# NEW_MD_-.net
KiCad netlist of a schematic drawn in EAGLE
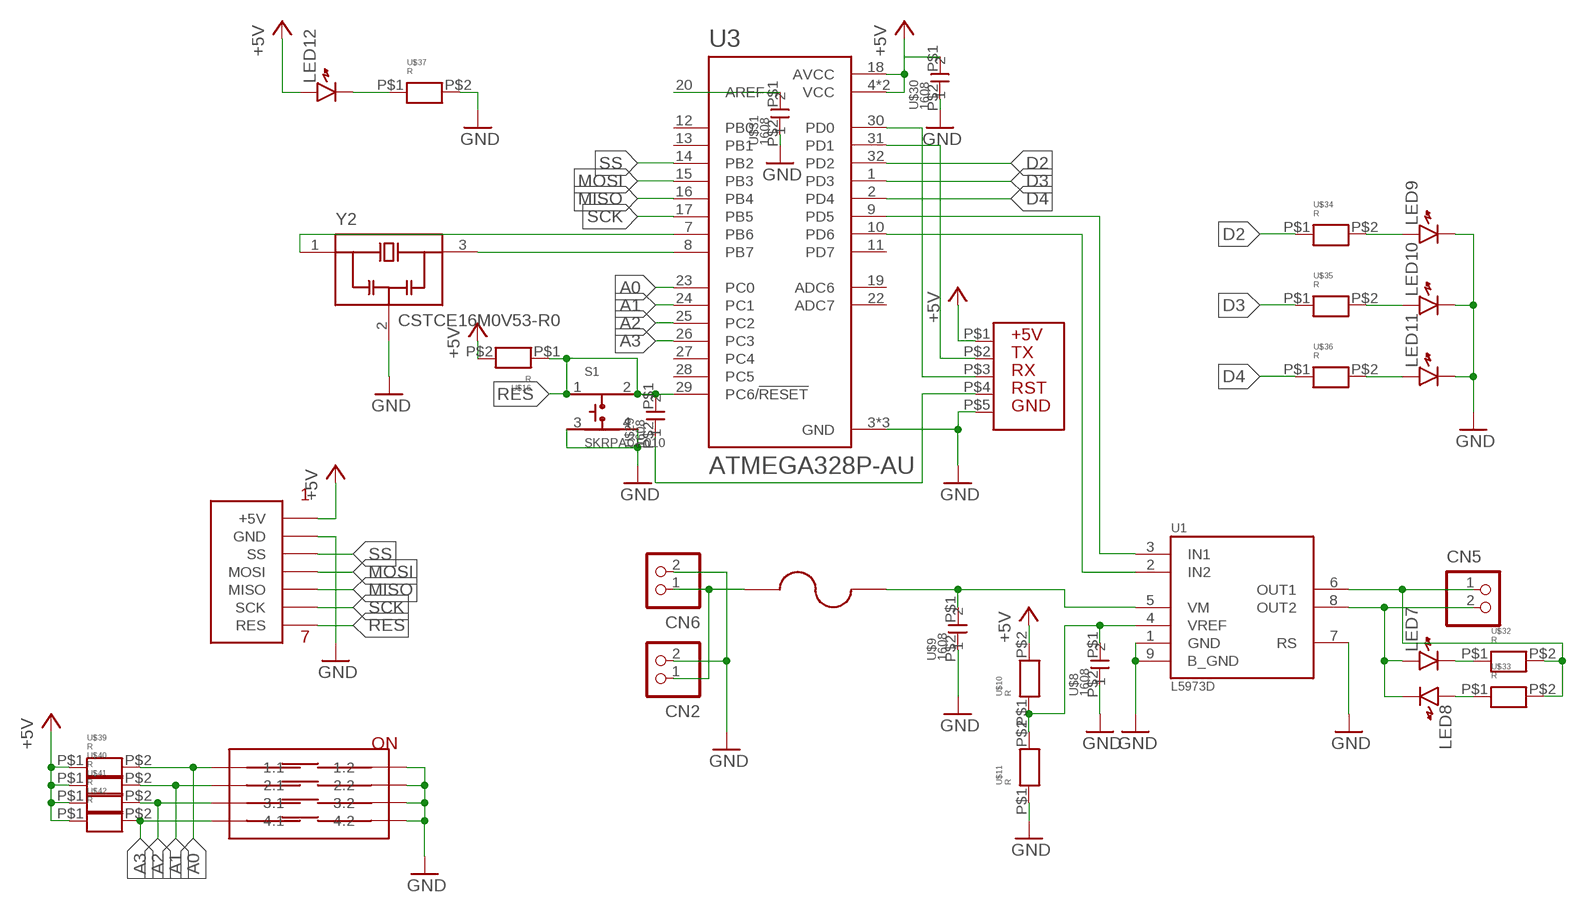
[diagram p0: schematic, sheet 1]

(export (version "E")
  (design (tool "Eeschema 10.0.6"))
  (components
    (comp (ref "CN2")
      (value "B2B-XH-A")
      (footprint "eagle-import:B2B-XH-A")
      (libsource (lib "eagle-import") (part "B2B-XH-A"))
    )
    (comp (ref "CN5")
      (value "S2B-XH-A")
      (footprint "eagle-import:S2B-XH-A")
      (libsource (lib "eagle-import") (part "S2B-XH-A"))
    )
    (comp (ref "CN6")
      (value "B2B-XH-A")
      (footprint "eagle-import:B2B-XH-A")
      (libsource (lib "eagle-import") (part "B2B-XH-A"))
    )
    (comp (ref "LED7")
      (value "LED1608")
      (footprint "eagle-import:LED1608")
      (libsource (lib "eagle-import") (part "LED1608"))
    )
    (comp (ref "LED8")
      (value "LED1608")
      (footprint "eagle-import:LED1608")
      (libsource (lib "eagle-import") (part "LED1608"))
    )
    (comp (ref "LED9")
      (value "LED1608")
      (footprint "eagle-import:LED1608")
      (libsource (lib "eagle-import") (part "LED1608"))
    )
    (comp (ref "LED10")
      (value "LED1608")
      (footprint "eagle-import:LED1608")
      (libsource (lib "eagle-import") (part "LED1608"))
    )
    (comp (ref "LED11")
      (value "LED1608")
      (footprint "eagle-import:LED1608")
      (libsource (lib "eagle-import") (part "LED1608"))
    )
    (comp (ref "LED12")
      (value "LED1608")
      (footprint "eagle-import:LED1608")
      (libsource (lib "eagle-import") (part "LED1608"))
    )
    (comp (ref "S1")
      (value "SKRPACE010")
      (footprint "eagle-import:SW_SKRPACE010")
      (fields (field (name "MF") "ALPS"))
      (libsource (lib "eagle-import") (part "SKRPACE010"))
    )
    (comp (ref "U$1")
      (value "FUSE3.7A")
      (footprint "eagle-import:FUSE3.7A")
      (libsource (lib "eagle-import") (part "FUSE3.7A"))
    )
    (comp (ref "U$8")
      (value "1608")
      (footprint "eagle-import:CON")
      (libsource (lib "eagle-import") (part "1608"))
    )
    (comp (ref "U$9")
      (value "1608")
      (footprint "eagle-import:CON")
      (libsource (lib "eagle-import") (part "1608"))
    )
    (comp (ref "U$10")
      (value "R")
      (footprint "eagle-import:1608")
      (libsource (lib "eagle-import") (part "R"))
    )
    (comp (ref "U$11")
      (value "R")
      (footprint "eagle-import:1608")
      (libsource (lib "eagle-import") (part "R"))
    )
    (comp (ref "U$16")
      (value "R")
      (footprint "eagle-import:1608")
      (libsource (lib "eagle-import") (part "R"))
    )
    (comp (ref "U$29")
      (value "1608")
      (footprint "eagle-import:CON")
      (libsource (lib "eagle-import") (part "1608"))
    )
    (comp (ref "U$30")
      (value "1608")
      (footprint "eagle-import:CON")
      (libsource (lib "eagle-import") (part "1608"))
    )
    (comp (ref "U$31")
      (value "1608")
      (footprint "eagle-import:CON")
      (libsource (lib "eagle-import") (part "1608"))
    )
    (comp (ref "U$32")
      (value "R")
      (footprint "eagle-import:1608")
      (libsource (lib "eagle-import") (part "R"))
    )
    (comp (ref "U$33")
      (value "R")
      (footprint "eagle-import:1608")
      (libsource (lib "eagle-import") (part "R"))
    )
    (comp (ref "U$34")
      (value "R")
      (footprint "eagle-import:1608")
      (libsource (lib "eagle-import") (part "R"))
    )
    (comp (ref "U$35")
      (value "R")
      (footprint "eagle-import:1608")
      (libsource (lib "eagle-import") (part "R"))
    )
    (comp (ref "U$36")
      (value "R")
      (footprint "eagle-import:1608")
      (libsource (lib "eagle-import") (part "R"))
    )
    (comp (ref "U$37")
      (value "R")
      (footprint "eagle-import:1608")
      (libsource (lib "eagle-import") (part "R"))
    )
    (comp (ref "U$38")
      (value "4P")
      (footprint "eagle-import:4P")
      (libsource (lib "eagle-import") (part "4P"))
    )
    (comp (ref "U$39")
      (value "R")
      (footprint "eagle-import:1608")
      (libsource (lib "eagle-import") (part "R"))
    )
    (comp (ref "U$40")
      (value "R")
      (footprint "eagle-import:1608")
      (libsource (lib "eagle-import") (part "R"))
    )
    (comp (ref "U$41")
      (value "R")
      (footprint "eagle-import:1608")
      (libsource (lib "eagle-import") (part "R"))
    )
    (comp (ref "U$42")
      (value "R")
      (footprint "eagle-import:1608")
      (libsource (lib "eagle-import") (part "R"))
    )
    (comp (ref "U$43")
      (value "SPI")
      (footprint "eagle-import:SPI")
      (libsource (lib "eagle-import") (part "SPI"))
    )
    (comp (ref "U$44")
      (value "SI")
      (footprint "eagle-import:SI")
      (libsource (lib "eagle-import") (part "SI"))
    )
    (comp (ref "U1")
      (value "L5973D")
      (footprint "eagle-import:SOIC127P600X170-9N")
      (fields (field (name "MF") "STMicroelectronics"))
      (libsource (lib "eagle-import") (part "L5973D"))
    )
    (comp (ref "U3")
      (value "ATMEGA328P-AU")
      (footprint "eagle-import:QFP80P900X900X120-32N")
      (fields (field (name "MF") "Microchip Technology"))
      (libsource (lib "eagle-import") (part "ATMEGA328P-AU"))
    )
    (comp (ref "Y2")
      (value "CSTCE16M0V53-R0")
      (footprint "eagle-import:OSC_CSTCE16M0V53-R0")
      (fields (field (name "MANUFACTURER") "Murata"))
      (libsource (lib "eagle-import") (part "CSTCE16M0V53-R0"))
    )
  )
  (nets
    (net (code "1") (name "+5V") (class "Default")
      (node (ref "LED12") (pin "A") (pinfunction "A_A") (pintype "passive"))
      (node (ref "U$10") (pin "P$2") (pinfunction "P$2_P$2") (pintype "bidirectional"))
      (node (ref "U$16") (pin "P$2") (pinfunction "P$2_P$2") (pintype "bidirectional"))
      (node (ref "U$30") (pin "P$1") (pinfunction "1_P$1") (pintype "bidirectional"))
      (node (ref "U$39") (pin "P$1") (pinfunction "P$1_P$1") (pintype "bidirectional"))
      (node (ref "U$40") (pin "P$1") (pinfunction "P$1_P$1") (pintype "bidirectional"))
      (node (ref "U$41") (pin "P$1") (pinfunction "P$1_P$1") (pintype "bidirectional"))
      (node (ref "U$42") (pin "P$1") (pinfunction "P$1_P$1") (pintype "bidirectional"))
      (node (ref "U$43") (pin "P$1") (pinfunction "+5V_P$1") (pintype "bidirectional"))
      (node (ref "U$44") (pin "P$1") (pinfunction "P$1_P$1") (pintype "bidirectional"))
      (node (ref "U3") (pin "18") (pinfunction "AVCC_18") (pintype "power_in"))
      (node (ref "U3") (pin "4") (pinfunction "VCC_4") (pintype "power_in"))
      (node (ref "U3") (pin "6") (pinfunction "VCC_6") (pintype "power_in"))
    )
    (net (code "2") (name "A0") (class "Default")
      (node (ref "U$38") (pin "1.1") (pinfunction "1.1_1.1") (pintype "bidirectional"))
      (node (ref "U$39") (pin "P$2") (pinfunction "P$2_P$2") (pintype "bidirectional"))
      (node (ref "U3") (pin "23") (pinfunction "PC0_23") (pintype "bidirectional"))
    )
    (net (code "3") (name "A1") (class "Default")
      (node (ref "U$38") (pin "2.1") (pinfunction "2.1_2.1") (pintype "bidirectional"))
      (node (ref "U$40") (pin "P$2") (pinfunction "P$2_P$2") (pintype "bidirectional"))
      (node (ref "U3") (pin "24") (pinfunction "PC1_24") (pintype "bidirectional"))
    )
    (net (code "4") (name "A2") (class "Default")
      (node (ref "U$38") (pin "3.1") (pinfunction "3.1_3.1") (pintype "bidirectional"))
      (node (ref "U$41") (pin "P$2") (pinfunction "P$2_P$2") (pintype "bidirectional"))
      (node (ref "U3") (pin "25") (pinfunction "PC2_25") (pintype "bidirectional"))
    )
    (net (code "5") (name "A3") (class "Default")
      (node (ref "U$38") (pin "4.1") (pinfunction "4.1_4.1") (pintype "bidirectional"))
      (node (ref "U$42") (pin "P$2") (pinfunction "P$2_P$2") (pintype "bidirectional"))
      (node (ref "U3") (pin "26") (pinfunction "PC3_26") (pintype "bidirectional"))
    )
    (net (code "6") (name "D2") (class "Default")
      (node (ref "U$34") (pin "P$1") (pinfunction "P$1_P$1") (pintype "bidirectional"))
      (node (ref "U3") (pin "32") (pinfunction "PD2_32") (pintype "bidirectional"))
    )
    (net (code "7") (name "D3") (class "Default")
      (node (ref "U$35") (pin "P$1") (pinfunction "P$1_P$1") (pintype "bidirectional"))
      (node (ref "U3") (pin "1") (pinfunction "PD3_1") (pintype "bidirectional"))
    )
    (net (code "8") (name "D4") (class "Default")
      (node (ref "U$36") (pin "P$1") (pinfunction "P$1_P$1") (pintype "bidirectional"))
      (node (ref "U3") (pin "2") (pinfunction "PD4_2") (pintype "bidirectional"))
    )
    (net (code "9") (name "GND") (class "Default")
      (node (ref "CN2") (pin "2") (pinfunction "2_2") (pintype "passive"))
      (node (ref "CN6") (pin "2") (pinfunction "2_2") (pintype "passive"))
      (node (ref "LED10") (pin "K") (pinfunction "K_K") (pintype "passive"))
      (node (ref "LED11") (pin "K") (pinfunction "K_K") (pintype "passive"))
      (node (ref "LED9") (pin "K") (pinfunction "K_K") (pintype "passive"))
      (node (ref "S1") (pin "3") (pinfunction "3_3") (pintype "bidirectional"))
      (node (ref "S1") (pin "4") (pinfunction "4_4") (pintype "bidirectional"))
      (node (ref "U$11") (pin "P$1") (pinfunction "P$1_P$1") (pintype "bidirectional"))
      (node (ref "U$30") (pin "P$2") (pinfunction "2_P$2") (pintype "bidirectional"))
      (node (ref "U$31") (pin "P$2") (pinfunction "2_P$2") (pintype "bidirectional"))
      (node (ref "U$37") (pin "P$2") (pinfunction "P$2_P$2") (pintype "bidirectional"))
      (node (ref "U$38") (pin "1.2") (pinfunction "1.2_1.2") (pintype "bidirectional"))
      (node (ref "U$38") (pin "2.2") (pinfunction "2.2_2.2") (pintype "bidirectional"))
      (node (ref "U$38") (pin "3.2") (pinfunction "3.2_3.2") (pintype "bidirectional"))
      (node (ref "U$38") (pin "4.2") (pinfunction "4.2_4.2") (pintype "bidirectional"))
      (node (ref "U$43") (pin "P$2") (pinfunction "GND_P$2") (pintype "bidirectional"))
      (node (ref "U$44") (pin "P$5") (pinfunction "P$5_P$5") (pintype "bidirectional"))
      (node (ref "U$8") (pin "P$2") (pinfunction "2_P$2") (pintype "bidirectional"))
      (node (ref "U$9") (pin "P$2") (pinfunction "2_P$2") (pintype "bidirectional"))
      (node (ref "U1") (pin "1") (pinfunction "GND_1") (pintype "output"))
      (node (ref "U1") (pin "7") (pinfunction "RS_7") (pintype "power_in"))
      (node (ref "U1") (pin "9") (pinfunction "B_GND_9") (pintype "power_in"))
      (node (ref "U3") (pin "21") (pinfunction "GND_21") (pintype "power_in"))
      (node (ref "U3") (pin "3") (pinfunction "GND_3") (pintype "power_in"))
      (node (ref "U3") (pin "5") (pinfunction "GND_5") (pintype "power_in"))
      (node (ref "Y2") (pin "2") (pinfunction "GND_2") (pintype "power_in"))
    )
    (net (code "10") (name "MISO") (class "Default")
      (node (ref "U$43") (pin "P$5") (pinfunction "MISO_P$5") (pintype "bidirectional"))
      (node (ref "U3") (pin "16") (pinfunction "PB4_16") (pintype "bidirectional"))
    )
    (net (code "11") (name "MOSI") (class "Default")
      (node (ref "U$43") (pin "P$4") (pinfunction "MOSI_P$4") (pintype "bidirectional"))
      (node (ref "U3") (pin "15") (pinfunction "PB3_15") (pintype "bidirectional"))
    )
    (net (code "12") (name "Net-(CN2-Pad1)") (class "Default")
      (node (ref "CN2") (pin "1") (pinfunction "1_1") (pintype "passive"))
      (node (ref "CN6") (pin "1") (pinfunction "1_1") (pintype "passive"))
      (node (ref "U$1") (pin "P$1") (pinfunction "P$1_P$1") (pintype "bidirectional"))
    )
    (net (code "13") (name "Net-(LED7-PadK)") (class "Default")
      (node (ref "LED7") (pin "K") (pinfunction "K_K") (pintype "passive"))
      (node (ref "U$32") (pin "P$1") (pinfunction "P$1_P$1") (pintype "bidirectional"))
    )
    (net (code "14") (name "Net-(LED8-PadA)") (class "Default")
      (node (ref "LED8") (pin "A") (pinfunction "A_A") (pintype "passive"))
      (node (ref "U$33") (pin "P$1") (pinfunction "P$1_P$1") (pintype "bidirectional"))
    )
    (net (code "15") (name "Net-(LED9-PadA)") (class "Default")
      (node (ref "LED9") (pin "A") (pinfunction "A_A") (pintype "passive"))
      (node (ref "U$34") (pin "P$2") (pinfunction "P$2_P$2") (pintype "bidirectional"))
    )
    (net (code "16") (name "Net-(LED10-PadA)") (class "Default")
      (node (ref "LED10") (pin "A") (pinfunction "A_A") (pintype "passive"))
      (node (ref "U$35") (pin "P$2") (pinfunction "P$2_P$2") (pintype "bidirectional"))
    )
    (net (code "17") (name "Net-(LED11-PadA)") (class "Default")
      (node (ref "LED11") (pin "A") (pinfunction "A_A") (pintype "passive"))
      (node (ref "U$36") (pin "P$2") (pinfunction "P$2_P$2") (pintype "bidirectional"))
    )
    (net (code "18") (name "Net-(LED12-PadK)") (class "Default")
      (node (ref "LED12") (pin "K") (pinfunction "K_K") (pintype "passive"))
      (node (ref "U$37") (pin "P$1") (pinfunction "P$1_P$1") (pintype "bidirectional"))
    )
    (net (code "19") (name "Net-(U$8-1)") (class "Default")
      (node (ref "U$10") (pin "P$1") (pinfunction "P$1_P$1") (pintype "bidirectional"))
      (node (ref "U$11") (pin "P$2") (pinfunction "P$2_P$2") (pintype "bidirectional"))
      (node (ref "U$8") (pin "P$1") (pinfunction "1_P$1") (pintype "bidirectional"))
      (node (ref "U1") (pin "4") (pinfunction "VREF_4") (pintype "output"))
    )
    (net (code "20") (name "Net-(U$9-1)") (class "Default")
      (node (ref "U$1") (pin "P$2") (pinfunction "P$2_P$2") (pintype "bidirectional"))
      (node (ref "U$9") (pin "P$1") (pinfunction "1_P$1") (pintype "bidirectional"))
      (node (ref "U1") (pin "5") (pinfunction "VM_5") (pintype "input"))
    )
    (net (code "21") (name "Net-(U$29-2)") (class "Default")
      (node (ref "U$29") (pin "P$2") (pinfunction "2_P$2") (pintype "bidirectional"))
      (node (ref "U$44") (pin "P$4") (pinfunction "P$4_P$4") (pintype "bidirectional"))
    )
    (net (code "22") (name "Net-(U$31-1)") (class "Default")
      (node (ref "U$31") (pin "P$1") (pinfunction "1_P$1") (pintype "bidirectional"))
      (node (ref "U3") (pin "20") (pinfunction "AREF_20") (pintype "input"))
    )
    (net (code "23") (name "Net-(U1-IN1)") (class "Default")
      (node (ref "U1") (pin "3") (pinfunction "IN1_3") (pintype "input"))
      (node (ref "U3") (pin "9") (pinfunction "PD5_9") (pintype "bidirectional"))
    )
    (net (code "24") (name "Net-(U1-IN2)") (class "Default")
      (node (ref "U1") (pin "2") (pinfunction "IN2_2") (pintype "bidirectional"))
      (node (ref "U3") (pin "10") (pinfunction "PD6_10") (pintype "bidirectional"))
    )
    (net (code "25") (name "Net-(U1-OUT1)") (class "Default")
      (node (ref "CN5") (pin "1") (pinfunction "1_1") (pintype "passive"))
      (node (ref "U$32") (pin "P$2") (pinfunction "P$2_P$2") (pintype "bidirectional"))
      (node (ref "U$33") (pin "P$2") (pinfunction "P$2_P$2") (pintype "bidirectional"))
      (node (ref "U1") (pin "6") (pinfunction "OUT1_6") (pintype "power_in"))
    )
    (net (code "26") (name "Net-(U1-OUT2)") (class "Default")
      (node (ref "CN5") (pin "2") (pinfunction "2_2") (pintype "passive"))
      (node (ref "LED7") (pin "A") (pinfunction "A_A") (pintype "passive"))
      (node (ref "LED8") (pin "K") (pinfunction "K_K") (pintype "passive"))
      (node (ref "U1") (pin "8") (pinfunction "OUT2_8") (pintype "power_in"))
    )
    (net (code "27") (name "Net-(U3-PB6)") (class "Default")
      (node (ref "U3") (pin "7") (pinfunction "PB6_7") (pintype "bidirectional"))
      (node (ref "Y2") (pin "1") (pinfunction "IN_1") (pintype "input"))
    )
    (net (code "28") (name "Net-(U3-PB7)") (class "Default")
      (node (ref "U3") (pin "8") (pinfunction "PB7_8") (pintype "bidirectional"))
      (node (ref "Y2") (pin "3") (pinfunction "OUT_3") (pintype "output"))
    )
    (net (code "29") (name "Net-(U3-PD0)") (class "Default")
      (node (ref "U$44") (pin "P$3") (pinfunction "P$3_P$3") (pintype "bidirectional"))
      (node (ref "U3") (pin "30") (pinfunction "PD0_30") (pintype "bidirectional"))
    )
    (net (code "30") (name "Net-(U3-PD1)") (class "Default")
      (node (ref "U$44") (pin "P$2") (pinfunction "P$2_P$2") (pintype "bidirectional"))
      (node (ref "U3") (pin "31") (pinfunction "PD1_31") (pintype "bidirectional"))
    )
    (net (code "31") (name "RES") (class "Default")
      (node (ref "S1") (pin "1") (pinfunction "1_1") (pintype "bidirectional"))
      (node (ref "S1") (pin "2") (pinfunction "2_2") (pintype "bidirectional"))
      (node (ref "U$16") (pin "P$1") (pinfunction "P$1_P$1") (pintype "bidirectional"))
      (node (ref "U$29") (pin "P$1") (pinfunction "1_P$1") (pintype "bidirectional"))
      (node (ref "U$43") (pin "P$7") (pinfunction "RES_P$7") (pintype "bidirectional"))
      (node (ref "U3") (pin "29") (pinfunction "PC6/~{RESET}_29") (pintype "bidirectional"))
    )
    (net (code "32") (name "SCK") (class "Default")
      (node (ref "U$43") (pin "P$6") (pinfunction "SCK_P$6") (pintype "bidirectional"))
      (node (ref "U3") (pin "17") (pinfunction "PB5_17") (pintype "bidirectional"))
    )
    (net (code "33") (name "SS") (class "Default")
      (node (ref "U$43") (pin "P$3") (pinfunction "SS_P$3") (pintype "bidirectional"))
      (node (ref "U3") (pin "14") (pinfunction "PB2_14") (pintype "bidirectional"))
    )
    (net (code "34") (name "unconnected-(U3-ADC6-Pad19)") (class "Default")
      (node (ref "U3") (pin "19") (pinfunction "ADC6_19") (pintype "bidirectional"))
    )
    (net (code "35") (name "unconnected-(U3-ADC7-Pad22)") (class "Default")
      (node (ref "U3") (pin "22") (pinfunction "ADC7_22") (pintype "bidirectional"))
    )
    (net (code "36") (name "unconnected-(U3-PB0-Pad12)") (class "Default")
      (node (ref "U3") (pin "12") (pinfunction "PB0_12") (pintype "bidirectional"))
    )
    (net (code "37") (name "unconnected-(U3-PB1-Pad13)") (class "Default")
      (node (ref "U3") (pin "13") (pinfunction "PB1_13") (pintype "bidirectional"))
    )
    (net (code "38") (name "unconnected-(U3-PC4-Pad27)") (class "Default")
      (node (ref "U3") (pin "27") (pinfunction "PC4_27") (pintype "bidirectional"))
    )
    (net (code "39") (name "unconnected-(U3-PC5-Pad28)") (class "Default")
      (node (ref "U3") (pin "28") (pinfunction "PC5_28") (pintype "bidirectional"))
    )
    (net (code "40") (name "unconnected-(U3-PD7-Pad11)") (class "Default")
      (node (ref "U3") (pin "11") (pinfunction "PD7_11") (pintype "bidirectional"))
    )
  )
)
